# supply.net
KiCad netlist of a schematic drawn in Altium Designer
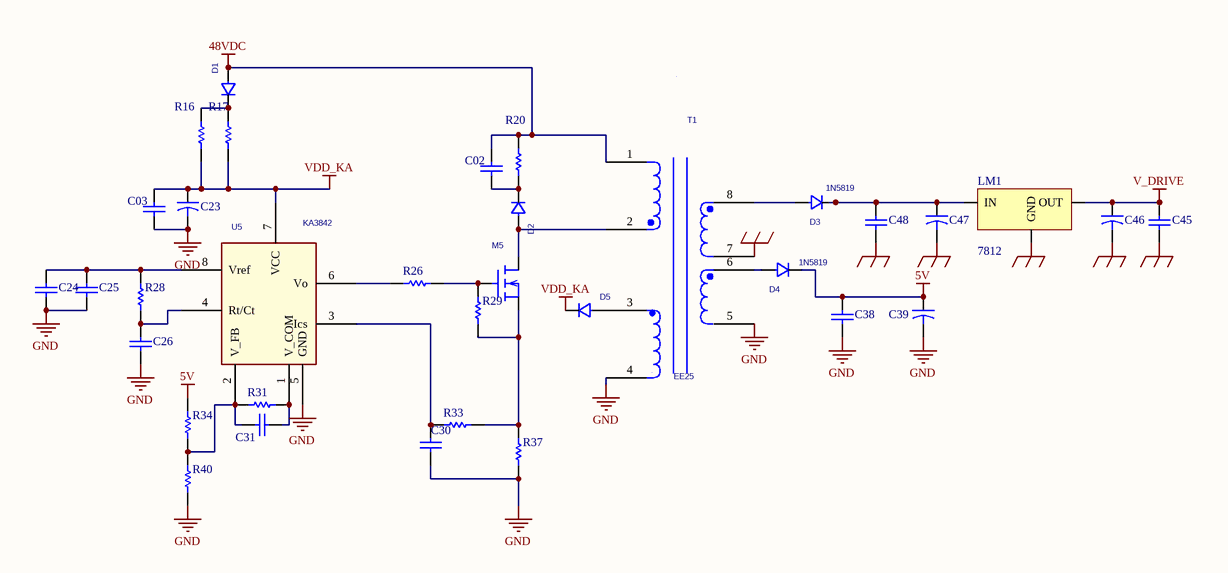
[diagram p0: supply.SchDoc]

(export (version "E")
  (design (tool "Eeschema 10.0.6"))
  (components
    (comp (ref "C02")
      (value "CX4")
      (footprint "C0805")
      (description "Capacitor Type 0805 SMD")
      (fields (field (name "PUBLISHER") "Altium Limited"))
      (libsource (lib "Miscellaneous Devices") (part "Cap"))
    )
    (comp (ref "C03")
      (value "CX4")
      (footprint "C0805")
      (description "Capacitor Type 0805 SMD")
      (fields (field (name "PUBLISHER") "Altium Limited"))
      (libsource (lib "Miscellaneous Devices") (part "Cap"))
    )
    (comp (ref "C23")
      (value "CAP SMD1206")
      (footprint "CAP_10uF_SMD")
      (description "Capacitor")
      (fields (field (name "PUBLISHER") "Altium Limited"))
      (libsource (lib "") (part "Cap2_1"))
    )
    (comp (ref "C24")
      (value "CX4")
      (footprint "C0805")
      (description "Capacitor Type 0805 SMD")
      (fields (field (name "PUBLISHER") "Altium Limited"))
      (libsource (lib "Miscellaneous Devices") (part "Cap"))
    )
    (comp (ref "C25")
      (value "CX4")
      (footprint "C0805")
      (description "Capacitor Type 0805 SMD")
      (fields (field (name "PUBLISHER") "Altium Limited"))
      (libsource (lib "Miscellaneous Devices") (part "Cap"))
    )
    (comp (ref "C26")
      (value "CX4")
      (footprint "C0805")
      (description "Capacitor Type 0805 SMD")
      (fields (field (name "PUBLISHER") "Altium Limited"))
      (libsource (lib "Miscellaneous Devices") (part "Cap"))
    )
    (comp (ref "C30")
      (value "CX4")
      (footprint "C0805")
      (description "Capacitor Type 0805 SMD")
      (fields (field (name "PUBLISHER") "Altium Limited"))
      (libsource (lib "Miscellaneous Devices") (part "Cap"))
    )
    (comp (ref "C31")
      (value "CX4")
      (footprint "C0805")
      (description "Capacitor Type 0805 SMD")
      (fields (field (name "PUBLISHER") "Altium Limited"))
      (libsource (lib "Miscellaneous Devices") (part "Cap"))
    )
    (comp (ref "C38")
      (value "CX4")
      (footprint "C0805")
      (description "Capacitor Type 0805 SMD")
      (fields (field (name "PUBLISHER") "Altium Limited"))
      (libsource (lib "Miscellaneous Devices") (part "Cap"))
    )
    (comp (ref "C39")
      (value "CAP SMD1206")
      (footprint "Tu470")
      (description "Capacitor")
      (fields (field (name "PUBLISHER") "Altium Limited"))
      (libsource (lib "") (part "Cap2_1"))
    )
    (comp (ref "C45")
      (value "CX4")
      (footprint "C0805")
      (description "Capacitor Type 0805 SMD")
      (fields (field (name "PUBLISHER") "Altium Limited"))
      (libsource (lib "Miscellaneous Devices") (part "Cap"))
    )
    (comp (ref "C46")
      (value "CAP SMD1206")
      (footprint "Tu470")
      (description "Capacitor")
      (fields (field (name "PUBLISHER") "Altium Limited"))
      (libsource (lib "Miscellaneous Devices") (part "Cap2"))
    )
    (comp (ref "C47")
      (value "CAP SMD1206")
      (footprint "Tu470")
      (description "Capacitor")
      (fields (field (name "PUBLISHER") "Altium Limited"))
      (libsource (lib "Miscellaneous Devices") (part "Cap2"))
    )
    (comp (ref "C48")
      (value "CX4")
      (footprint "C0805")
      (description "Capacitor Type 0805 SMD")
      (fields (field (name "PUBLISHER") "Altium Limited"))
      (libsource (lib "Miscellaneous Devices") (part "Cap"))
    )
    (comp (ref "D1") (value "FR107") (footprint "DIODE5819_V1") (libsource (lib "*") (part "1N4148")))
    (comp (ref "D2") (value "FR107") (footprint "DIODE5819_V1") (libsource (lib "") (part "1N4148_1")))
    (comp (ref "D3") (value "1N5819") (footprint "DIODE5819_V1") (libsource (lib "") (part "1N4148_1")))
    (comp (ref "D4") (value "1N5819") (footprint "DIODE5819_V1") (libsource (lib "") (part "1N4148_1")))
    (comp (ref "D5") (value "1N5819") (footprint "DIODE5819_V1") (libsource (lib "") (part "1N4148_1")))
    (comp (ref "LM1") (value "7812") (footprint "TO220AB") (libsource (lib "LM7812") (part "Component_1")))
    (comp (ref "M5") (value "IRF640") (footprint "TO220AB") (libsource (lib "*") (part "IRF540_Dup1")))
    (comp (ref "R16")
      (value "Resistor SMD0805")
      (footprint "R0805")
      (fields (field (name "PUBLISHER") "Altium Limited"))
      (libsource (lib "Miscellaneous Devices") (part "Res1"))
    )
    (comp (ref "R17")
      (value "Resistor SMD0805")
      (footprint "R0805")
      (fields (field (name "PUBLISHER") "Altium Limited"))
      (libsource (lib "Miscellaneous Devices") (part "Res1"))
    )
    (comp (ref "R20")
      (value "Resistor SMD0805")
      (footprint "R0805")
      (fields (field (name "PUBLISHER") "Altium Limited"))
      (libsource (lib "Miscellaneous Devices") (part "Res1"))
    )
    (comp (ref "R26")
      (value "Resistor SMD0805")
      (footprint "R0805")
      (fields (field (name "PUBLISHER") "Altium Limited"))
      (libsource (lib "Miscellaneous Devices") (part "Res1"))
    )
    (comp (ref "R28")
      (value "Resistor SMD0805")
      (footprint "R0805")
      (fields (field (name "PUBLISHER") "Altium Limited"))
      (libsource (lib "Miscellaneous Devices") (part "Res1"))
    )
    (comp (ref "R29")
      (value "Resistor SMD0805")
      (footprint "R0805")
      (fields (field (name "PUBLISHER") "Altium Limited"))
      (libsource (lib "Miscellaneous Devices") (part "Res1"))
    )
    (comp (ref "R31")
      (value "Resistor SMD0805")
      (footprint "R0805")
      (fields (field (name "PUBLISHER") "Altium Limited"))
      (libsource (lib "Miscellaneous Devices") (part "Res1"))
    )
    (comp (ref "R33")
      (value "Resistor SMD0805")
      (footprint "R0805")
      (fields (field (name "PUBLISHER") "Altium Limited"))
      (libsource (lib "Miscellaneous Devices") (part "Res1"))
    )
    (comp (ref "R34")
      (value "Resistor SMD0805")
      (footprint "R0805")
      (fields (field (name "PUBLISHER") "Altium Limited"))
      (libsource (lib "Miscellaneous Devices") (part "Res1"))
    )
    (comp (ref "R37")
      (value "Resistor SMD0805")
      (footprint "R0805")
      (fields (field (name "PUBLISHER") "Altium Limited"))
      (libsource (lib "Miscellaneous Devices") (part "Res1"))
    )
    (comp (ref "R40")
      (value "Resistor SMD0805")
      (footprint "R0805")
      (fields (field (name "PUBLISHER") "Altium Limited"))
      (libsource (lib "Miscellaneous Devices") (part "Res1"))
    )
    (comp (ref "T1") (value "EE25") (footprint "TRANSFORMER") (libsource (lib "*") (part "TRAN_FBP1S4/SM_5")))
    (comp (ref "U5") (value "KA3842") (footprint "SOIC_8PIN") (libsource (lib "*") (part "KA3842_1")))
  )
  (nets
    (net (code "1") (name "5V") (class "Default")
      (node (ref "C38") (pin "1") (pinfunction "1_1") (pintype "passive"))
      (node (ref "C39") (pin "1") (pinfunction "1_1") (pintype "passive"))
      (node (ref "D4") (pin "1") (pinfunction "1_1") (pintype "passive"))
      (node (ref "R34") (pin "2") (pinfunction "2_2") (pintype "passive"))
    )
    (net (code "2") (name "48VDC") (class "Default")
      (node (ref "C02") (pin "1") (pinfunction "1_1") (pintype "passive"))
      (node (ref "D1") (pin "1") (pinfunction "1_1") (pintype "passive"))
      (node (ref "R20") (pin "1") (pinfunction "1_1") (pintype "passive"))
      (node (ref "T1") (pin "1") (pinfunction "1_1") (pintype "passive"))
    )
    (net (code "3") (name "GND") (class "Default")
      (node (ref "C03") (pin "2") (pinfunction "2_2") (pintype "passive"))
      (node (ref "C23") (pin "2") (pinfunction "2_2") (pintype "passive"))
      (node (ref "C24") (pin "2") (pinfunction "2_2") (pintype "passive"))
      (node (ref "C25") (pin "2") (pinfunction "2_2") (pintype "passive"))
      (node (ref "C26") (pin "2") (pinfunction "2_2") (pintype "passive"))
      (node (ref "C30") (pin "1") (pinfunction "1_1") (pintype "passive"))
      (node (ref "C38") (pin "2") (pinfunction "2_2") (pintype "passive"))
      (node (ref "C39") (pin "2") (pinfunction "2_2") (pintype "passive"))
      (node (ref "R37") (pin "2") (pinfunction "2_2") (pintype "passive"))
      (node (ref "R40") (pin "1") (pinfunction "1_1") (pintype "passive"))
      (node (ref "T1") (pin "4") (pinfunction "4_4") (pintype "passive"))
      (node (ref "T1") (pin "5") (pinfunction "5_5") (pintype "passive"))
      (node (ref "U5") (pin "5") (pinfunction "GND_5") (pintype "passive"))
    )
    (net (code "4") (name "GND_EARTH") (class "Default")
      (node (ref "C45") (pin "2") (pinfunction "2_2") (pintype "passive"))
      (node (ref "C46") (pin "2") (pinfunction "2_2") (pintype "passive"))
      (node (ref "C47") (pin "2") (pinfunction "2_2") (pintype "passive"))
      (node (ref "C48") (pin "2") (pinfunction "2_2") (pintype "passive"))
      (node (ref "LM1") (pin "2") (pinfunction "GND_2") (pintype "passive"))
      (node (ref "T1") (pin "7") (pinfunction "7_7") (pintype "passive"))
    )
    (net (code "5") (name "Net-(C02-Pad2)") (class "Default")
      (node (ref "C02") (pin "2") (pinfunction "2_2") (pintype "passive"))
      (node (ref "D2") (pin "1") (pinfunction "1_1") (pintype "passive"))
      (node (ref "R20") (pin "2") (pinfunction "2_2") (pintype "passive"))
    )
    (net (code "6") (name "Net-(D1-Pad2)") (class "Default")
      (node (ref "D1") (pin "2") (pinfunction "2_2") (pintype "passive"))
      (node (ref "R16") (pin "1") (pinfunction "1_1") (pintype "passive"))
      (node (ref "R17") (pin "1") (pinfunction "1_1") (pintype "passive"))
    )
    (net (code "7") (name "Net-(D3-Pad2)") (class "Default")
      (node (ref "D3") (pin "2") (pinfunction "2_2") (pintype "passive"))
      (node (ref "T1") (pin "8") (pinfunction "8_8") (pintype "passive"))
    )
    (net (code "8") (name "Net-(D4-Pad2)") (class "Default")
      (node (ref "D4") (pin "2") (pinfunction "2_2") (pintype "passive"))
      (node (ref "T1") (pin "6") (pinfunction "6_6") (pintype "passive"))
    )
    (net (code "9") (name "Net-(D5-Pad2)") (class "Default")
      (node (ref "D5") (pin "2") (pinfunction "2_2") (pintype "passive"))
      (node (ref "T1") (pin "3") (pinfunction "3_3") (pintype "passive"))
    )
    (net (code "10") (name "Net-(LM1-IN)") (class "Default")
      (node (ref "C47") (pin "1") (pinfunction "1_1") (pintype "passive"))
      (node (ref "C48") (pin "1") (pinfunction "1_1") (pintype "passive"))
      (node (ref "D3") (pin "1") (pinfunction "1_1") (pintype "passive"))
      (node (ref "LM1") (pin "1") (pinfunction "IN_1") (pintype "passive"))
    )
    (net (code "11") (name "Net-(M5-d)") (class "Default")
      (node (ref "D2") (pin "2") (pinfunction "2_2") (pintype "passive"))
      (node (ref "M5") (pin "2") (pinfunction "d_2") (pintype "passive"))
      (node (ref "T1") (pin "2") (pinfunction "2_2") (pintype "passive"))
    )
    (net (code "12") (name "Net-(M5-g)") (class "Default")
      (node (ref "M5") (pin "1") (pinfunction "g_1") (pintype "passive"))
      (node (ref "R26") (pin "1") (pinfunction "1_1") (pintype "passive"))
      (node (ref "R29") (pin "1") (pinfunction "1_1") (pintype "passive"))
    )
    (net (code "13") (name "Net-(M5-s)") (class "Default")
      (node (ref "M5") (pin "3") (pinfunction "s_3") (pintype "passive"))
      (node (ref "R29") (pin "2") (pinfunction "2_2") (pintype "passive"))
      (node (ref "R33") (pin "2") (pinfunction "2_2") (pintype "passive"))
      (node (ref "R37") (pin "1") (pinfunction "1_1") (pintype "passive"))
    )
    (net (code "14") (name "Net-(U5-Ics)") (class "Default")
      (node (ref "C30") (pin "2") (pinfunction "2_2") (pintype "passive"))
      (node (ref "R33") (pin "1") (pinfunction "1_1") (pintype "passive"))
      (node (ref "U5") (pin "3") (pinfunction "Ics_3") (pintype "passive"))
    )
    (net (code "15") (name "Net-(U5-Rt{slash}Ct)") (class "Default")
      (node (ref "C26") (pin "1") (pinfunction "1_1") (pintype "passive"))
      (node (ref "R28") (pin "1") (pinfunction "1_1") (pintype "passive"))
      (node (ref "U5") (pin "4") (pinfunction "Rt/Ct_4") (pintype "passive"))
    )
    (net (code "16") (name "Net-(U5-V_COM)") (class "Default")
      (node (ref "C31") (pin "1") (pinfunction "1_1") (pintype "passive"))
      (node (ref "R31") (pin "2") (pinfunction "2_2") (pintype "passive"))
      (node (ref "U5") (pin "1") (pinfunction "V_COM_1") (pintype "passive"))
    )
    (net (code "17") (name "Net-(U5-V_FB)") (class "Default")
      (node (ref "C31") (pin "2") (pinfunction "2_2") (pintype "passive"))
      (node (ref "R31") (pin "1") (pinfunction "1_1") (pintype "passive"))
      (node (ref "R34") (pin "1") (pinfunction "1_1") (pintype "passive"))
      (node (ref "R40") (pin "2") (pinfunction "2_2") (pintype "passive"))
      (node (ref "U5") (pin "2") (pinfunction "V_FB_2") (pintype "passive"))
    )
    (net (code "18") (name "Net-(U5-Vo)") (class "Default")
      (node (ref "R26") (pin "2") (pinfunction "2_2") (pintype "passive"))
      (node (ref "U5") (pin "6") (pinfunction "Vo_6") (pintype "passive"))
    )
    (net (code "19") (name "Net-(U5-Vref)") (class "Default")
      (node (ref "C24") (pin "1") (pinfunction "1_1") (pintype "passive"))
      (node (ref "C25") (pin "1") (pinfunction "1_1") (pintype "passive"))
      (node (ref "R28") (pin "2") (pinfunction "2_2") (pintype "passive"))
      (node (ref "U5") (pin "8") (pinfunction "Vref_8") (pintype "passive"))
    )
    (net (code "20") (name "VDD_KA") (class "Default")
      (node (ref "C03") (pin "1") (pinfunction "1_1") (pintype "passive"))
      (node (ref "C23") (pin "1") (pinfunction "1_1") (pintype "passive"))
      (node (ref "D5") (pin "1") (pinfunction "1_1") (pintype "passive"))
      (node (ref "R16") (pin "2") (pinfunction "2_2") (pintype "passive"))
      (node (ref "R17") (pin "2") (pinfunction "2_2") (pintype "passive"))
      (node (ref "U5") (pin "7") (pinfunction "VCC_7") (pintype "passive"))
    )
    (net (code "21") (name "V_DRIVE") (class "Default")
      (node (ref "C45") (pin "1") (pinfunction "1_1") (pintype "passive"))
      (node (ref "C46") (pin "1") (pinfunction "1_1") (pintype "passive"))
      (node (ref "LM1") (pin "3") (pinfunction "OUT_3") (pintype "passive"))
    )
  )
)
